# Regulator_5V0_to_3V3.net
KiCad netlist of a schematic drawn in Altium Designer
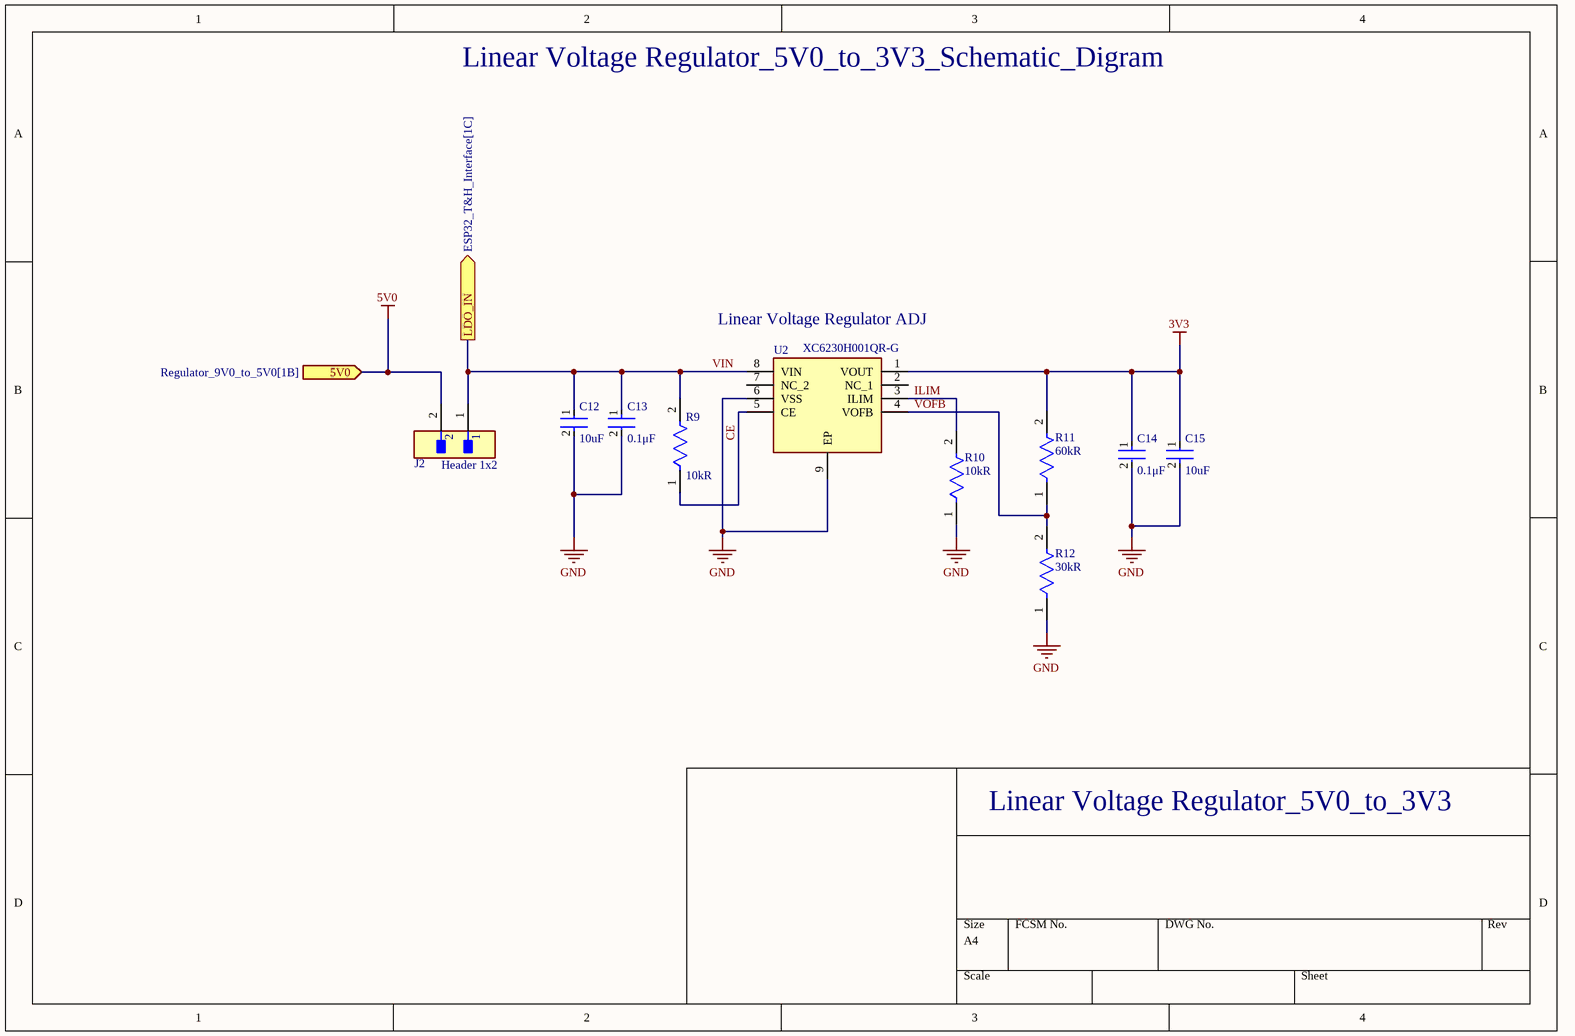
[diagram p0: Regulator_5V0_to_3V3.SchDoc]

(export (version "E")
  (design (tool "Eeschema 10.0.6"))
  (components
    (comp (ref "C12")
      (value "C1608X5R1A106M080AC")
      (footprint "FP-C1608-080-0_1-IPC_A")
      (description "Multilayer Ceramic Capacitors 10μF ±20% 10V X5R SMD 0603")
      (fields (field (name "CAPACITANCE") "10uF") (field (name "TOLERANCE") "20%"))
      (libsource (lib "Altium Content Vault") (part "236180d848d6139a670b325ea6854c9"))
    )
    (comp (ref "C13")
      (value "C0603C104K8RACTU")
      (footprint "FP-C0603C-CF-MFG")
      (description "CAP CER 0.1UF 10V X7R 0603")
      (fields
        (field (name "TOLERANCE") "0.1")
        (field (name "OCTOPART") "https://octopart.com/c0603c104k8ractu-kemet-145075")
        (field (name "CAPACITANCE") "0.1μF")
      )
      (libsource (lib "Altium Content Vault") (part "b4654b650e69147ec39a6b967a45e02"))
    )
    (comp (ref "C14")
      (value "C0603C104K8RACTU")
      (footprint "FP-C0603C-CF-MFG")
      (description "CAP CER 0.1UF 10V X7R 0603")
      (fields
        (field (name "TOLERANCE") "0.1")
        (field (name "OCTOPART") "https://octopart.com/c0603c104k8ractu-kemet-145075")
        (field (name "CAPACITANCE") "0.1μF")
      )
      (libsource (lib "Altium Content Vault") (part "b4654b650e69147ec39a6b967a45e02"))
    )
    (comp (ref "C15")
      (value "C1608X5R1A106M080AC")
      (footprint "FP-C1608-080-0_1-IPC_A")
      (description "Multilayer Ceramic Capacitors 10μF ±20% 10V X5R SMD 0603")
      (fields (field (name "CAPACITANCE") "10uF") (field (name "TOLERANCE") "20%"))
      (libsource (lib "Altium Content Vault") (part "236180d848d6139a670b325ea6854c9"))
    )
    (comp (ref "J2")
      (value "Header 1x2")
      (footprint "FP-M20-9990245-MFG")
      (description "CONN HEADER VERT 2POS 2.54MM")
      (fields (field (name "VOLTAGE") "50V"))
      (libsource (lib "Altium Content Vault") (part "3bc925449376181038e59eaffc5286c"))
    )
    (comp (ref "R9")
      (value "AC0402FR-0710KL")
      (footprint "FP-AC0402-MFG")
      (description "RES 10kΩ ±1% 0.063W 0402")
      (fields (field (name "TOLERANCE") "1%") (field (name "RESISTANCE") "10kR"))
      (libsource (lib "Altium Content Vault") (part "1029c3af85768c4190bb7ad29bc67b5"))
    )
    (comp (ref "R10")
      (value "AC0402FR-0710KL")
      (footprint "FP-AC0402-MFG")
      (description "RES 10kΩ ±1% 0.063W 0402")
      (fields (field (name "TOLERANCE") "1%") (field (name "RESISTANCE") "10kR"))
      (libsource (lib "Altium Content Vault") (part "1029c3af85768c4190bb7ad29bc67b5"))
    )
    (comp (ref "R11")
      (value "MCR01MRTF3002")
      (footprint "FP-MCR01-IPC_A")
      (description "Thick Film Chip Resistor, 0402, 60kΩ, 1%, 100ppm/°C, 0.063W, 50V")
      (fields (field (name "TOLERANCE") "1%") (field (name "RESISTANCE") "60kR"))
      (libsource (lib "Altium Content Vault") (part "1029c3af85768c4190bb7ad29bc67b5"))
    )
    (comp (ref "R12")
      (value "MCR01MRTF3002")
      (footprint "FP-MCR01-IPC_A")
      (description "Thick Film Chip Resistor, 0402, 30kΩ, 1%, 100ppm/°C, 0.063W, 50V")
      (fields (field (name "TOLERANCE") "1%") (field (name "RESISTANCE") "30kR"))
      (libsource (lib "Altium Content Vault") (part "1029c3af85768c4190bb7ad29bc67b5"))
    )
    (comp (ref "U2")
      (value "XC6230H001QR-G")
      (footprint "XC6230H001")
      (description "Integrated Circuit")
      (fields (field (name "MOUSER PART NUMBER") "865-XC6230H001QR-G"))
      (libsource (lib "XC6230H001") (part "XC6230H001QR-G"))
    )
  )
  (nets
    (net (code "1") (name "/CE") (class "Default")
      (node (ref "R9") (pin "1") (pinfunction "1_1") (pintype "passive"))
      (node (ref "U2") (pin "5") (pinfunction "CE_5") (pintype "passive"))
    )
    (net (code "2") (name "/ILIM") (class "Default")
      (node (ref "R10") (pin "2") (pinfunction "2_2") (pintype "passive"))
      (node (ref "U2") (pin "3") (pinfunction "ILIM_3") (pintype "passive"))
    )
    (net (code "3") (name "/VIN") (class "Default")
      (node (ref "C12") (pin "1") (pinfunction "1_1") (pintype "passive"))
      (node (ref "C13") (pin "1") (pinfunction "1_1") (pintype "passive"))
      (node (ref "J2") (pin "1") (pinfunction "1_1") (pintype "passive"))
      (node (ref "R9") (pin "2") (pinfunction "2_2") (pintype "passive"))
      (node (ref "U2") (pin "8") (pinfunction "VIN_8") (pintype "passive"))
    )
    (net (code "4") (name "/VOFB") (class "Default")
      (node (ref "R11") (pin "1") (pinfunction "1_1") (pintype "passive"))
      (node (ref "R12") (pin "2") (pinfunction "2_2") (pintype "passive"))
      (node (ref "U2") (pin "4") (pinfunction "VOFB_4") (pintype "passive"))
    )
    (net (code "5") (name "3V3") (class "Default")
      (node (ref "C14") (pin "1") (pinfunction "1_1") (pintype "passive"))
      (node (ref "C15") (pin "1") (pinfunction "1_1") (pintype "passive"))
      (node (ref "R11") (pin "2") (pinfunction "2_2") (pintype "passive"))
      (node (ref "U2") (pin "1") (pinfunction "VOUT_1") (pintype "passive"))
    )
    (net (code "6") (name "5V0") (class "Default")
      (node (ref "J2") (pin "2") (pinfunction "2_2") (pintype "passive"))
    )
    (net (code "7") (name "GND") (class "Default")
      (node (ref "C12") (pin "2") (pinfunction "2_2") (pintype "passive"))
      (node (ref "C13") (pin "2") (pinfunction "2_2") (pintype "passive"))
      (node (ref "C14") (pin "2") (pinfunction "2_2") (pintype "passive"))
      (node (ref "C15") (pin "2") (pinfunction "2_2") (pintype "passive"))
      (node (ref "R10") (pin "1") (pinfunction "1_1") (pintype "passive"))
      (node (ref "R12") (pin "1") (pinfunction "1_1") (pintype "passive"))
      (node (ref "U2") (pin "6") (pinfunction "VSS_6") (pintype "passive"))
      (node (ref "U2") (pin "9") (pinfunction "EP_9") (pintype "passive"))
    )
    (net (code "8") (name "unconnected-(U2-NC_1-Pad2)") (class "Default")
      (node (ref "U2") (pin "2") (pinfunction "NC_1_2") (pintype "passive"))
    )
    (net (code "9") (name "unconnected-(U2-NC_2-Pad7)") (class "Default")
      (node (ref "U2") (pin "7") (pinfunction "NC_2_7") (pintype "passive"))
    )
  )
)
